# DWM3000.net
KiCad netlist of a schematic drawn in Altium Designer
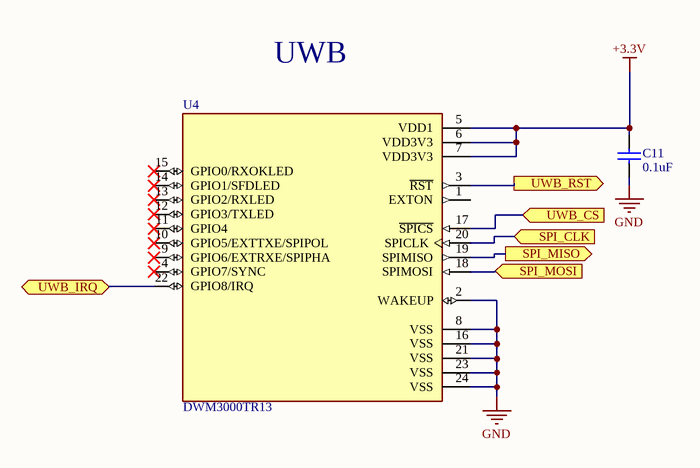
[diagram p0: DWM3000.SchDoc]

(export (version "E")
  (design (tool "Eeschema 10.0.6"))
  (components
    (comp (ref "C11")
      (value "0.1uF")
      (footprint "CAPC1005X55N")
      (description "Capacitor")
      (fields (field (name "Comment") "Cap") (field (name "PUBLISHER") "Altium Limited"))
      (libsource (lib "Miscellaneous Devices") (part "Cap"))
    )
    (comp (ref "U4")
      (value "DWM3000TR13")
      (footprint "XCVR_DWM3000TR13")
      (fields (field (name "MF") "Qorvo"))
      (libsource (lib "DWM3000TR13") (part "DWM3000TR13"))
    )
  )
  (nets
    (net (code "1") (name "+3.3V") (class "Default")
      (node (ref "C11") (pin "2") (pinfunction "2_2") (pintype "passive"))
      (node (ref "U4") (pin "5") (pinfunction "VDD1_5") (pintype "power_in"))
      (node (ref "U4") (pin "6") (pinfunction "VDD3V3_6") (pintype "power_in"))
      (node (ref "U4") (pin "7") (pinfunction "VDD3V3_7") (pintype "power_in"))
    )
    (net (code "2") (name "/SPI_CLK") (class "Default")
      (node (ref "U4") (pin "20") (pinfunction "SPICLK_20") (pintype "input"))
    )
    (net (code "3") (name "/SPI_MISO") (class "Default")
      (node (ref "U4") (pin "19") (pinfunction "SPIMISO_19") (pintype "output"))
    )
    (net (code "4") (name "/SPI_MOSI") (class "Default")
      (node (ref "U4") (pin "18") (pinfunction "SPIMOSI_18") (pintype "input"))
    )
    (net (code "5") (name "/UWB_CS") (class "Default")
      (node (ref "U4") (pin "17") (pinfunction "~{SPICS}_17") (pintype "input"))
    )
    (net (code "6") (name "/UWB_IRQ") (class "Default")
      (node (ref "U4") (pin "22") (pinfunction "GPIO8/IRQ_22") (pintype "bidirectional"))
    )
    (net (code "7") (name "/UWB_RST") (class "Default")
      (node (ref "U4") (pin "3") (pinfunction "~{RST}_3") (pintype "output"))
    )
    (net (code "8") (name "GND") (class "Default")
      (node (ref "C11") (pin "1") (pinfunction "1_1") (pintype "passive"))
      (node (ref "U4") (pin "16") (pinfunction "VSS_16") (pintype "power_in"))
      (node (ref "U4") (pin "2") (pinfunction "WAKEUP_2") (pintype "bidirectional"))
      (node (ref "U4") (pin "21") (pinfunction "VSS_21") (pintype "power_in"))
      (node (ref "U4") (pin "23") (pinfunction "VSS_23") (pintype "power_in"))
      (node (ref "U4") (pin "24") (pinfunction "VSS_24") (pintype "power_in"))
      (node (ref "U4") (pin "8") (pinfunction "VSS_8") (pintype "power_in"))
    )
    (net (code "9") (name "unconnected-(U4-EXTON-Pad1)") (class "Default")
      (node (ref "U4") (pin "1") (pinfunction "EXTON_1") (pintype "output"))
    )
    (net (code "10") (name "unconnected-(U4-GPIO0{slash}RXOKLED-Pad15)") (class "Default")
      (node (ref "U4") (pin "15") (pinfunction "GPIO0/RXOKLED_15") (pintype "bidirectional+no_connect"))
    )
    (net (code "11") (name "unconnected-(U4-GPIO1{slash}SFDLED-Pad14)") (class "Default")
      (node (ref "U4") (pin "14") (pinfunction "GPIO1/SFDLED_14") (pintype "bidirectional+no_connect"))
    )
    (net (code "12") (name "unconnected-(U4-GPIO2{slash}RXLED-Pad13)") (class "Default")
      (node (ref "U4") (pin "13") (pinfunction "GPIO2/RXLED_13") (pintype "bidirectional+no_connect"))
    )
    (net (code "13") (name "unconnected-(U4-GPIO3{slash}TXLED-Pad12)") (class "Default")
      (node (ref "U4") (pin "12") (pinfunction "GPIO3/TXLED_12") (pintype "bidirectional+no_connect"))
    )
    (net (code "14") (name "unconnected-(U4-GPIO4-Pad11)") (class "Default")
      (node (ref "U4") (pin "11") (pinfunction "GPIO4_11") (pintype "bidirectional+no_connect"))
    )
    (net (code "15") (name "unconnected-(U4-GPIO5{slash}EXTTXE{slash}SPIPOL-Pad10)") (class "Default")
      (node (ref "U4") (pin "10") (pinfunction "GPIO5/EXTTXE/SPIPOL_10") (pintype "bidirectional+no_connect"))
    )
    (net (code "16") (name "unconnected-(U4-GPIO6{slash}EXTRXE{slash}SPIPHA-Pad9)") (class "Default")
      (node (ref "U4") (pin "9") (pinfunction "GPIO6/EXTRXE/SPIPHA_9") (pintype "bidirectional+no_connect"))
    )
    (net (code "17") (name "unconnected-(U4-GPIO7{slash}SYNC-Pad4)") (class "Default")
      (node (ref "U4") (pin "4") (pinfunction "GPIO7/SYNC_4") (pintype "bidirectional+no_connect"))
    )
  )
)
